# BC_proto.net
KiCad netlist of a schematic drawn in EAGLE
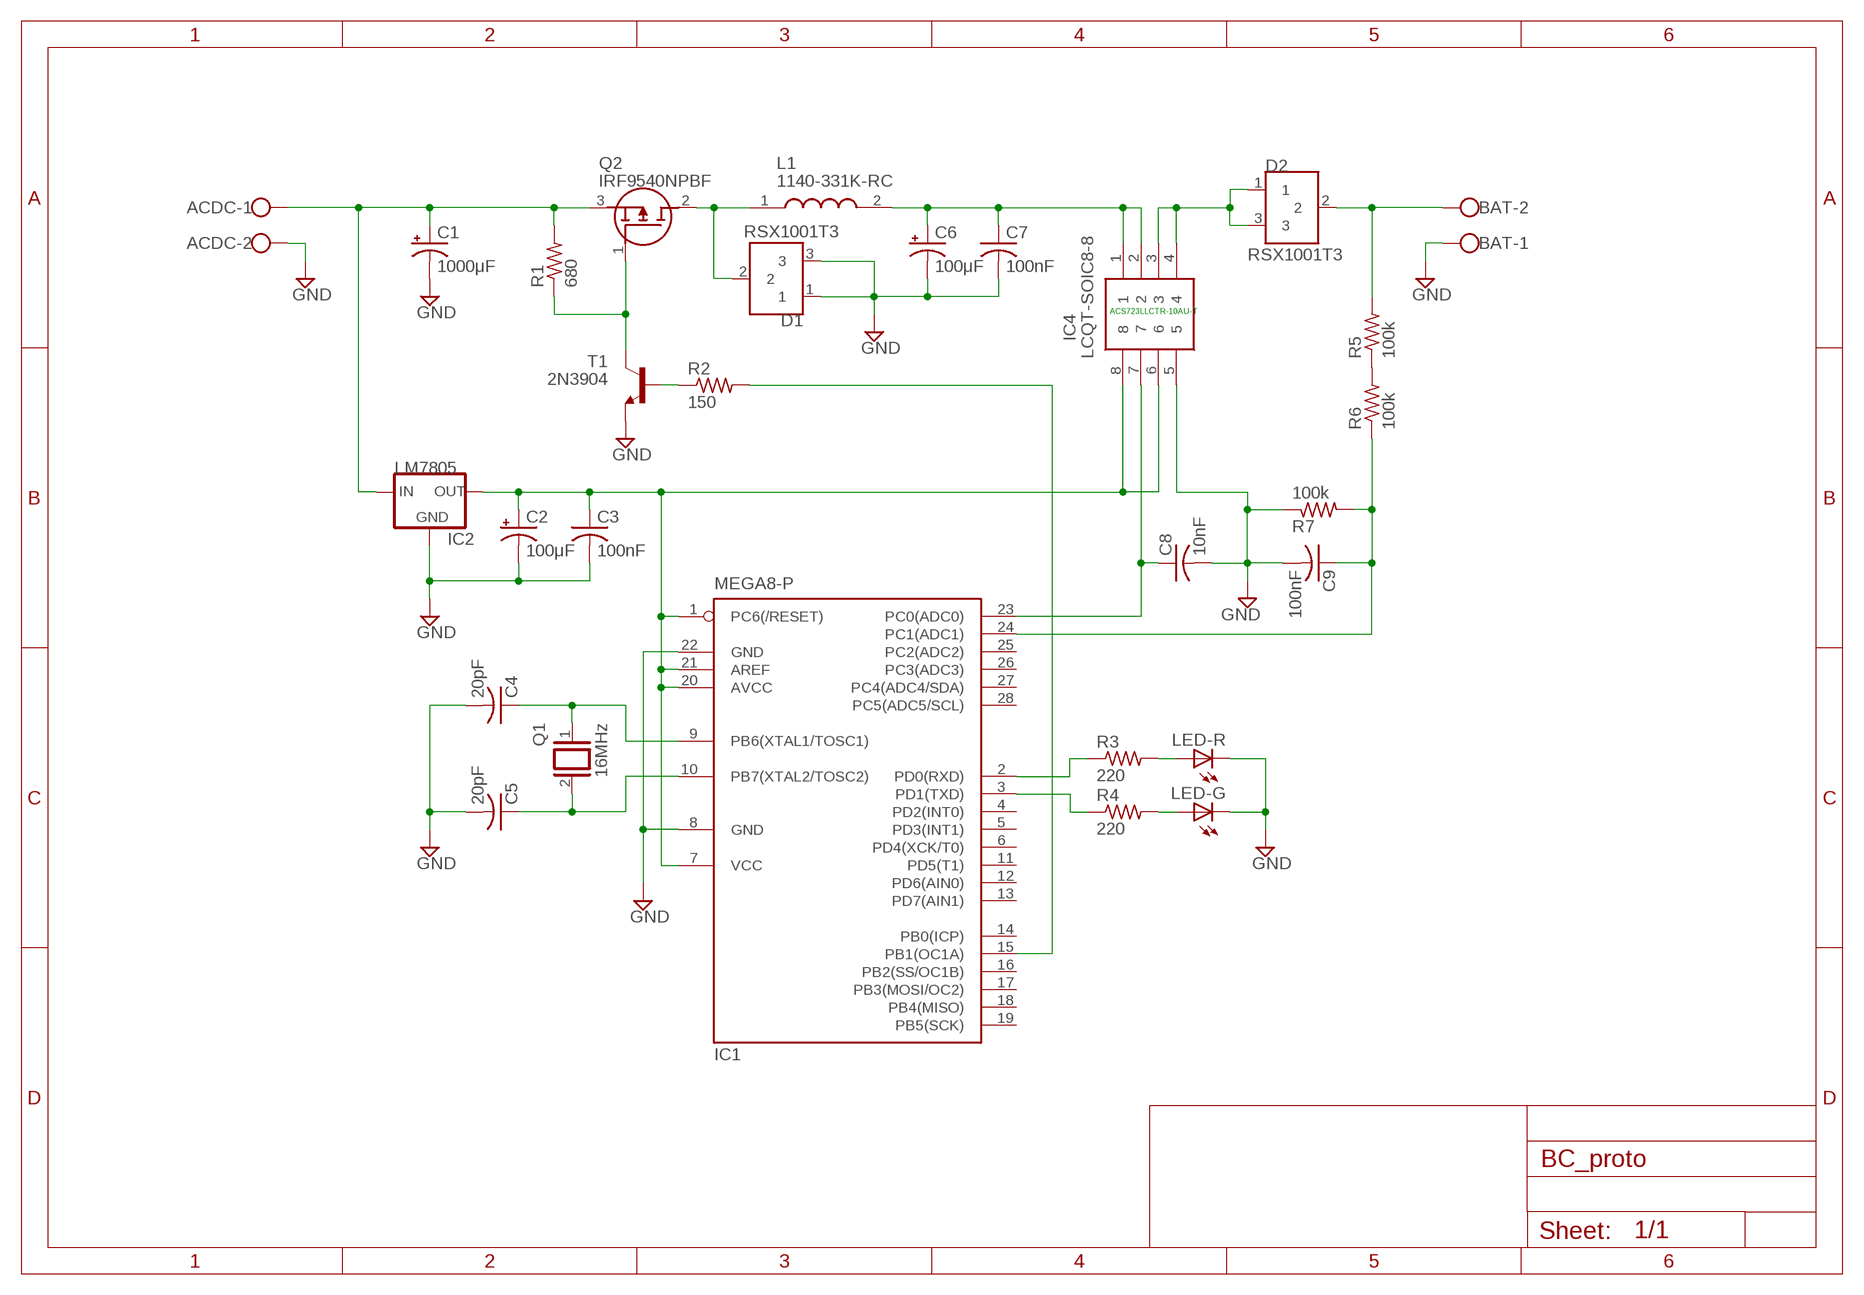
[diagram p0: schematic, sheet 1]

(export (version "E")
  (design (tool "Eeschema 10.0.6"))
  (components
    (comp (ref "ACDC")
      (value "W237-102")
      (footprint "eagle-import:W237-102")
      (fields (field (name "MPN") "237-102"))
      (libsource (lib "eagle-import") (part "W237-102"))
    )
    (comp (ref "BAT")
      (value "W237-102")
      (footprint "eagle-import:W237-102")
      (fields (field (name "MPN") "237-102"))
      (libsource (lib "eagle-import") (part "W237-102"))
    )
    (comp (ref "C1")
      (value "1000μF")
      (footprint "eagle-import:E7,5-16")
      (libsource (lib "eagle-import") (part "CPOL-USE7.5-16"))
    )
    (comp (ref "C2")
      (value "100μF")
      (footprint "eagle-import:E2,5-6E")
      (libsource (lib "eagle-import") (part "CPOL-USE2,5-6E"))
    )
    (comp (ref "C3")
      (value "100nF")
      (footprint "eagle-import:C050-024X044")
      (libsource (lib "eagle-import") (part "C-US050-024X044"))
    )
    (comp (ref "C4")
      (value "20pF")
      (footprint "eagle-import:C050-024X044")
      (libsource (lib "eagle-import") (part "C-US050-024X044"))
    )
    (comp (ref "C5")
      (value "20pF")
      (footprint "eagle-import:C050-024X044")
      (libsource (lib "eagle-import") (part "C-US050-024X044"))
    )
    (comp (ref "C6")
      (value "100μF")
      (footprint "eagle-import:E2,5-6E")
      (libsource (lib "eagle-import") (part "CPOL-USE2,5-6E"))
    )
    (comp (ref "C7")
      (value "100nF")
      (footprint "eagle-import:C050-024X044")
      (libsource (lib "eagle-import") (part "C-US050-024X044"))
    )
    (comp (ref "C8")
      (value "10nF")
      (footprint "eagle-import:C050-024X044")
      (libsource (lib "eagle-import") (part "C-US050-024X044"))
    )
    (comp (ref "C9")
      (value "100nF")
      (footprint "eagle-import:C050-024X044")
      (libsource (lib "eagle-import") (part "C-US050-024X044"))
    )
    (comp (ref "D1")
      (value "RSX1001T3")
      (footprint "eagle-import:RSX1001T3")
      (libsource (lib "eagle-import") (part "RSX1001T3"))
    )
    (comp (ref "D2")
      (value "RSX1001T3")
      (footprint "eagle-import:RSX1001T3")
      (libsource (lib "eagle-import") (part "RSX1001T3"))
    )
    (comp (ref "IC1")
      (value "MEGA8-P")
      (footprint "eagle-import:DIL28-3")
      (libsource (lib "eagle-import") (part "MEGA8-P"))
    )
    (comp (ref "IC2")
      (value "LM7805")
      (footprint "eagle-import:78XXS")
      (libsource (lib "eagle-import") (part "78XXS"))
    )
    (comp (ref "IC4")
      (value "LCQT-SOIC8-8")
      (footprint "eagle-import:DIPS762W46P254L1016H160Q8N")
      (fields (field (name "ARROW_PART_NUMBER") "W9501RC") (field (name "RS_PART_NUMBER") "1582878"))
      (libsource (lib "eagle-import") (part "W9501RC"))
    )
    (comp (ref "L1")
      (value "1140-331K-RC")
      (footprint "eagle-import:1140-331K-RC")
      (fields (field (name "RS_PART_NUMBER") "1728697"))
      (libsource (lib "eagle-import") (part "1140-331K-RC"))
    )
    (comp (ref "LED-G")
      (value "TLLR4400")
      (footprint "eagle-import:LED3MM")
      (fields (field (name "MF") "VISHAY SEMICONDUCTOR"))
      (libsource (lib "eagle-import") (part "TLLR4400"))
    )
    (comp (ref "LED-R")
      (value "TLLR4400")
      (footprint "eagle-import:LED3MM")
      (fields (field (name "MF") "VISHAY SEMICONDUCTOR"))
      (libsource (lib "eagle-import") (part "TLLR4400"))
    )
    (comp (ref "Q1")
      (value "16MHz")
      (footprint "eagle-import:QS")
      (libsource (lib "eagle-import") (part "XTAL/S"))
    )
    (comp (ref "Q2")
      (value "IRF9540NPBF")
      (footprint "eagle-import:TO254P469X1042X1967-3P")
      (fields (field (name "RS_PART_NUMBER") "5411225P"))
      (libsource (lib "eagle-import") (part "IRF9540NPBF"))
    )
    (comp (ref "R1")
      (value "680")
      (footprint "eagle-import:0204_7")
      (libsource (lib "eagle-import") (part "R-US_0204/7"))
    )
    (comp (ref "R2")
      (value "150")
      (footprint "eagle-import:0204_7")
      (libsource (lib "eagle-import") (part "R-US_0204/7"))
    )
    (comp (ref "R3")
      (value "220")
      (footprint "eagle-import:0204_7")
      (libsource (lib "eagle-import") (part "R-US_0204/7"))
    )
    (comp (ref "R4")
      (value "220")
      (footprint "eagle-import:0204_7")
      (libsource (lib "eagle-import") (part "R-US_0204/7"))
    )
    (comp (ref "R5")
      (value "100k")
      (footprint "eagle-import:0204_7")
      (libsource (lib "eagle-import") (part "R-US_0204/7"))
    )
    (comp (ref "R6")
      (value "100k")
      (footprint "eagle-import:0204_7")
      (libsource (lib "eagle-import") (part "R-US_0204/7"))
    )
    (comp (ref "R7")
      (value "100k")
      (footprint "eagle-import:0204_7")
      (libsource (lib "eagle-import") (part "R-US_0204/7"))
    )
    (comp (ref "T1")
      (value "2N3904")
      (footprint "eagle-import:TO92")
      (libsource (lib "eagle-import") (part "2N3904"))
    )
  )
  (nets
    (net (code "1") (name "GND") (class "Default")
      (node (ref "ACDC") (pin "2") (pinfunction "KL_2") (pintype "passive"))
      (node (ref "BAT") (pin "1") (pinfunction "KL_1") (pintype "passive"))
      (node (ref "C1") (pin "-") (pinfunction "-_-") (pintype "passive"))
      (node (ref "C2") (pin "-") (pinfunction "-_-") (pintype "passive"))
      (node (ref "C3") (pin "2") (pinfunction "2_2") (pintype "passive"))
      (node (ref "C4") (pin "2") (pinfunction "2_2") (pintype "passive"))
      (node (ref "C5") (pin "2") (pinfunction "2_2") (pintype "passive"))
      (node (ref "C6") (pin "-") (pinfunction "-_-") (pintype "passive"))
      (node (ref "C7") (pin "2") (pinfunction "2_2") (pintype "passive"))
      (node (ref "C8") (pin "2") (pinfunction "2_2") (pintype "passive"))
      (node (ref "C9") (pin "2") (pinfunction "2_2") (pintype "passive"))
      (node (ref "D1") (pin "1") (pinfunction "1_1") (pintype "input"))
      (node (ref "D1") (pin "3") (pinfunction "3_3") (pintype "input"))
      (node (ref "IC1") (pin "22") (pinfunction "GND_22") (pintype "power_in"))
      (node (ref "IC1") (pin "8") (pinfunction "GND_8") (pintype "power_in"))
      (node (ref "IC2") (pin "GND") (pinfunction "GND_GND") (pintype "input"))
      (node (ref "IC4") (pin "5") (pinfunction "5_5") (pintype "bidirectional"))
      (node (ref "LED-G") (pin "K") (pinfunction "C_K") (pintype "passive"))
      (node (ref "LED-R") (pin "K") (pinfunction "C_K") (pintype "passive"))
      (node (ref "R7") (pin "1") (pinfunction "1_1") (pintype "passive"))
      (node (ref "T1") (pin "3") (pinfunction "E_3") (pintype "passive"))
    )
    (net (code "2") (name "Net-(ACDCA-KL)") (class "Default")
      (node (ref "ACDC") (pin "1") (pinfunction "KL_1") (pintype "passive"))
      (node (ref "C1") (pin "+") (pinfunction "+_+") (pintype "passive"))
      (node (ref "IC2") (pin "IN") (pinfunction "IN_IN") (pintype "input"))
      (node (ref "Q2") (pin "3") (pinfunction "S_3") (pintype "power_in"))
      (node (ref "R1") (pin "2") (pinfunction "2_2") (pintype "passive"))
    )
    (net (code "3") (name "Net-(BATB-KL)") (class "Default")
      (node (ref "BAT") (pin "2") (pinfunction "KL_2") (pintype "passive"))
      (node (ref "D2") (pin "2") (pinfunction "2_2") (pintype "output"))
      (node (ref "R5") (pin "2") (pinfunction "2_2") (pintype "passive"))
    )
    (net (code "4") (name "Net-(C6-Pad+)") (class "Default")
      (node (ref "C6") (pin "+") (pinfunction "+_+") (pintype "passive"))
      (node (ref "C7") (pin "1") (pinfunction "1_1") (pintype "passive"))
      (node (ref "IC4") (pin "1") (pinfunction "1_1") (pintype "bidirectional"))
      (node (ref "IC4") (pin "2") (pinfunction "2_2") (pintype "input"))
      (node (ref "L1") (pin "2") (pinfunction "2_2") (pintype "bidirectional"))
    )
    (net (code "5") (name "Net-(D2-Pad1)") (class "Default")
      (node (ref "D2") (pin "1") (pinfunction "1_1") (pintype "input"))
      (node (ref "D2") (pin "3") (pinfunction "3_3") (pintype "input"))
      (node (ref "IC4") (pin "3") (pinfunction "3_3") (pintype "input"))
      (node (ref "IC4") (pin "4") (pinfunction "4_4") (pintype "power_in"))
    )
    (net (code "6") (name "Net-(IC1-AREF)") (class "Default")
      (node (ref "C2") (pin "+") (pinfunction "+_+") (pintype "passive"))
      (node (ref "C3") (pin "1") (pinfunction "1_1") (pintype "passive"))
      (node (ref "IC1") (pin "1") (pinfunction "PC6(/RESET)_1") (pintype "bidirectional"))
      (node (ref "IC1") (pin "20") (pinfunction "AVCC_20") (pintype "power_in"))
      (node (ref "IC1") (pin "21") (pinfunction "AREF_21") (pintype "passive"))
      (node (ref "IC1") (pin "7") (pinfunction "VCC_7") (pintype "power_in"))
      (node (ref "IC2") (pin "OUT") (pinfunction "OUT_OUT") (pintype "passive"))
      (node (ref "IC4") (pin "6") (pinfunction "6_6") (pintype "output"))
      (node (ref "IC4") (pin "8") (pinfunction "8_8") (pintype "power_in"))
    )
    (net (code "7") (name "Net-(IC1-PB1(OC1A))") (class "Default")
      (node (ref "IC1") (pin "15") (pinfunction "PB1(OC1A)_15") (pintype "bidirectional"))
      (node (ref "R2") (pin "2") (pinfunction "2_2") (pintype "passive"))
    )
    (net (code "8") (name "Net-(IC1-PB6(XTAL1{slash}TOSC1))") (class "Default")
      (node (ref "C4") (pin "1") (pinfunction "1_1") (pintype "passive"))
      (node (ref "IC1") (pin "9") (pinfunction "PB6(XTAL1/TOSC1)_9") (pintype "bidirectional"))
      (node (ref "Q1") (pin "1") (pinfunction "1_1") (pintype "passive"))
    )
    (net (code "9") (name "Net-(IC1-PB7(XTAL2{slash}TOSC2))") (class "Default")
      (node (ref "C5") (pin "1") (pinfunction "1_1") (pintype "passive"))
      (node (ref "IC1") (pin "10") (pinfunction "PB7(XTAL2/TOSC2)_10") (pintype "bidirectional"))
      (node (ref "Q1") (pin "2") (pinfunction "2_2") (pintype "passive"))
    )
    (net (code "10") (name "Net-(IC1-PC0(ADC0))") (class "Default")
      (node (ref "C8") (pin "1") (pinfunction "1_1") (pintype "passive"))
      (node (ref "IC1") (pin "23") (pinfunction "PC0(ADC0)_23") (pintype "bidirectional"))
      (node (ref "IC4") (pin "7") (pinfunction "7_7") (pintype "power_in"))
    )
    (net (code "11") (name "Net-(IC1-PC1(ADC1))") (class "Default")
      (node (ref "C9") (pin "1") (pinfunction "1_1") (pintype "passive"))
      (node (ref "IC1") (pin "24") (pinfunction "PC1(ADC1)_24") (pintype "bidirectional"))
      (node (ref "R6") (pin "1") (pinfunction "1_1") (pintype "passive"))
      (node (ref "R7") (pin "2") (pinfunction "2_2") (pintype "passive"))
    )
    (net (code "12") (name "Net-(IC1-PD0(RXD))") (class "Default")
      (node (ref "IC1") (pin "2") (pinfunction "PD0(RXD)_2") (pintype "bidirectional"))
      (node (ref "R3") (pin "1") (pinfunction "1_1") (pintype "passive"))
    )
    (net (code "13") (name "Net-(IC1-PD1(TXD))") (class "Default")
      (node (ref "IC1") (pin "3") (pinfunction "PD1(TXD)_3") (pintype "bidirectional"))
      (node (ref "R4") (pin "1") (pinfunction "1_1") (pintype "passive"))
    )
    (net (code "14") (name "Net-(LED-G-PadA)") (class "Default")
      (node (ref "LED-G") (pin "A") (pinfunction "A_A") (pintype "passive"))
      (node (ref "R4") (pin "2") (pinfunction "2_2") (pintype "passive"))
    )
    (net (code "15") (name "Net-(LED-R-PadA)") (class "Default")
      (node (ref "LED-R") (pin "A") (pinfunction "A_A") (pintype "passive"))
      (node (ref "R3") (pin "2") (pinfunction "2_2") (pintype "passive"))
    )
    (net (code "16") (name "Net-(Q2-D)") (class "Default")
      (node (ref "D1") (pin "2") (pinfunction "2_2") (pintype "output"))
      (node (ref "L1") (pin "1") (pinfunction "1_1") (pintype "bidirectional"))
      (node (ref "Q2") (pin "2") (pinfunction "D_2") (pintype "output"))
    )
    (net (code "17") (name "Net-(Q2-G)") (class "Default")
      (node (ref "Q2") (pin "1") (pinfunction "G_1") (pintype "power_in"))
      (node (ref "R1") (pin "1") (pinfunction "1_1") (pintype "passive"))
      (node (ref "T1") (pin "1") (pinfunction "C_1") (pintype "passive"))
    )
    (net (code "18") (name "Net-(R5-Pad1)") (class "Default")
      (node (ref "R5") (pin "1") (pinfunction "1_1") (pintype "passive"))
      (node (ref "R6") (pin "2") (pinfunction "2_2") (pintype "passive"))
    )
    (net (code "19") (name "Net-(T1-B)") (class "Default")
      (node (ref "R2") (pin "1") (pinfunction "1_1") (pintype "passive"))
      (node (ref "T1") (pin "2") (pinfunction "B_2") (pintype "passive"))
    )
    (net (code "20") (name "unconnected-(IC1-PB0(ICP)-Pad14)") (class "Default")
      (node (ref "IC1") (pin "14") (pinfunction "PB0(ICP)_14") (pintype "bidirectional"))
    )
    (net (code "21") (name "unconnected-(IC1-PB2(SS{slash}OC1B)-Pad16)") (class "Default")
      (node (ref "IC1") (pin "16") (pinfunction "PB2(SS/OC1B)_16") (pintype "bidirectional"))
    )
    (net (code "22") (name "unconnected-(IC1-PB3(MOSI{slash}OC2)-Pad17)") (class "Default")
      (node (ref "IC1") (pin "17") (pinfunction "PB3(MOSI/OC2)_17") (pintype "bidirectional"))
    )
    (net (code "23") (name "unconnected-(IC1-PB4(MISO)-Pad18)") (class "Default")
      (node (ref "IC1") (pin "18") (pinfunction "PB4(MISO)_18") (pintype "bidirectional"))
    )
    (net (code "24") (name "unconnected-(IC1-PB5(SCK)-Pad19)") (class "Default")
      (node (ref "IC1") (pin "19") (pinfunction "PB5(SCK)_19") (pintype "bidirectional"))
    )
    (net (code "25") (name "unconnected-(IC1-PC2(ADC2)-Pad25)") (class "Default")
      (node (ref "IC1") (pin "25") (pinfunction "PC2(ADC2)_25") (pintype "bidirectional"))
    )
    (net (code "26") (name "unconnected-(IC1-PC3(ADC3)-Pad26)") (class "Default")
      (node (ref "IC1") (pin "26") (pinfunction "PC3(ADC3)_26") (pintype "bidirectional"))
    )
    (net (code "27") (name "unconnected-(IC1-PC4(ADC4{slash}SDA)-Pad27)") (class "Default")
      (node (ref "IC1") (pin "27") (pinfunction "PC4(ADC4/SDA)_27") (pintype "bidirectional"))
    )
    (net (code "28") (name "unconnected-(IC1-PC5(ADC5{slash}SCL)-Pad28)") (class "Default")
      (node (ref "IC1") (pin "28") (pinfunction "PC5(ADC5/SCL)_28") (pintype "bidirectional"))
    )
    (net (code "29") (name "unconnected-(IC1-PD2(INT0)-Pad4)") (class "Default")
      (node (ref "IC1") (pin "4") (pinfunction "PD2(INT0)_4") (pintype "bidirectional"))
    )
    (net (code "30") (name "unconnected-(IC1-PD3(INT1)-Pad5)") (class "Default")
      (node (ref "IC1") (pin "5") (pinfunction "PD3(INT1)_5") (pintype "bidirectional"))
    )
    (net (code "31") (name "unconnected-(IC1-PD4(XCK{slash}T0)-Pad6)") (class "Default")
      (node (ref "IC1") (pin "6") (pinfunction "PD4(XCK/T0)_6") (pintype "bidirectional"))
    )
    (net (code "32") (name "unconnected-(IC1-PD5(T1)-Pad11)") (class "Default")
      (node (ref "IC1") (pin "11") (pinfunction "PD5(T1)_11") (pintype "bidirectional"))
    )
    (net (code "33") (name "unconnected-(IC1-PD6(AIN0)-Pad12)") (class "Default")
      (node (ref "IC1") (pin "12") (pinfunction "PD6(AIN0)_12") (pintype "bidirectional"))
    )
    (net (code "34") (name "unconnected-(IC1-PD7(AIN1)-Pad13)") (class "Default")
      (node (ref "IC1") (pin "13") (pinfunction "PD7(AIN1)_13") (pintype "bidirectional"))
    )
  )
)
